# Hub.net
KiCad netlist of a schematic drawn in Altium Designer
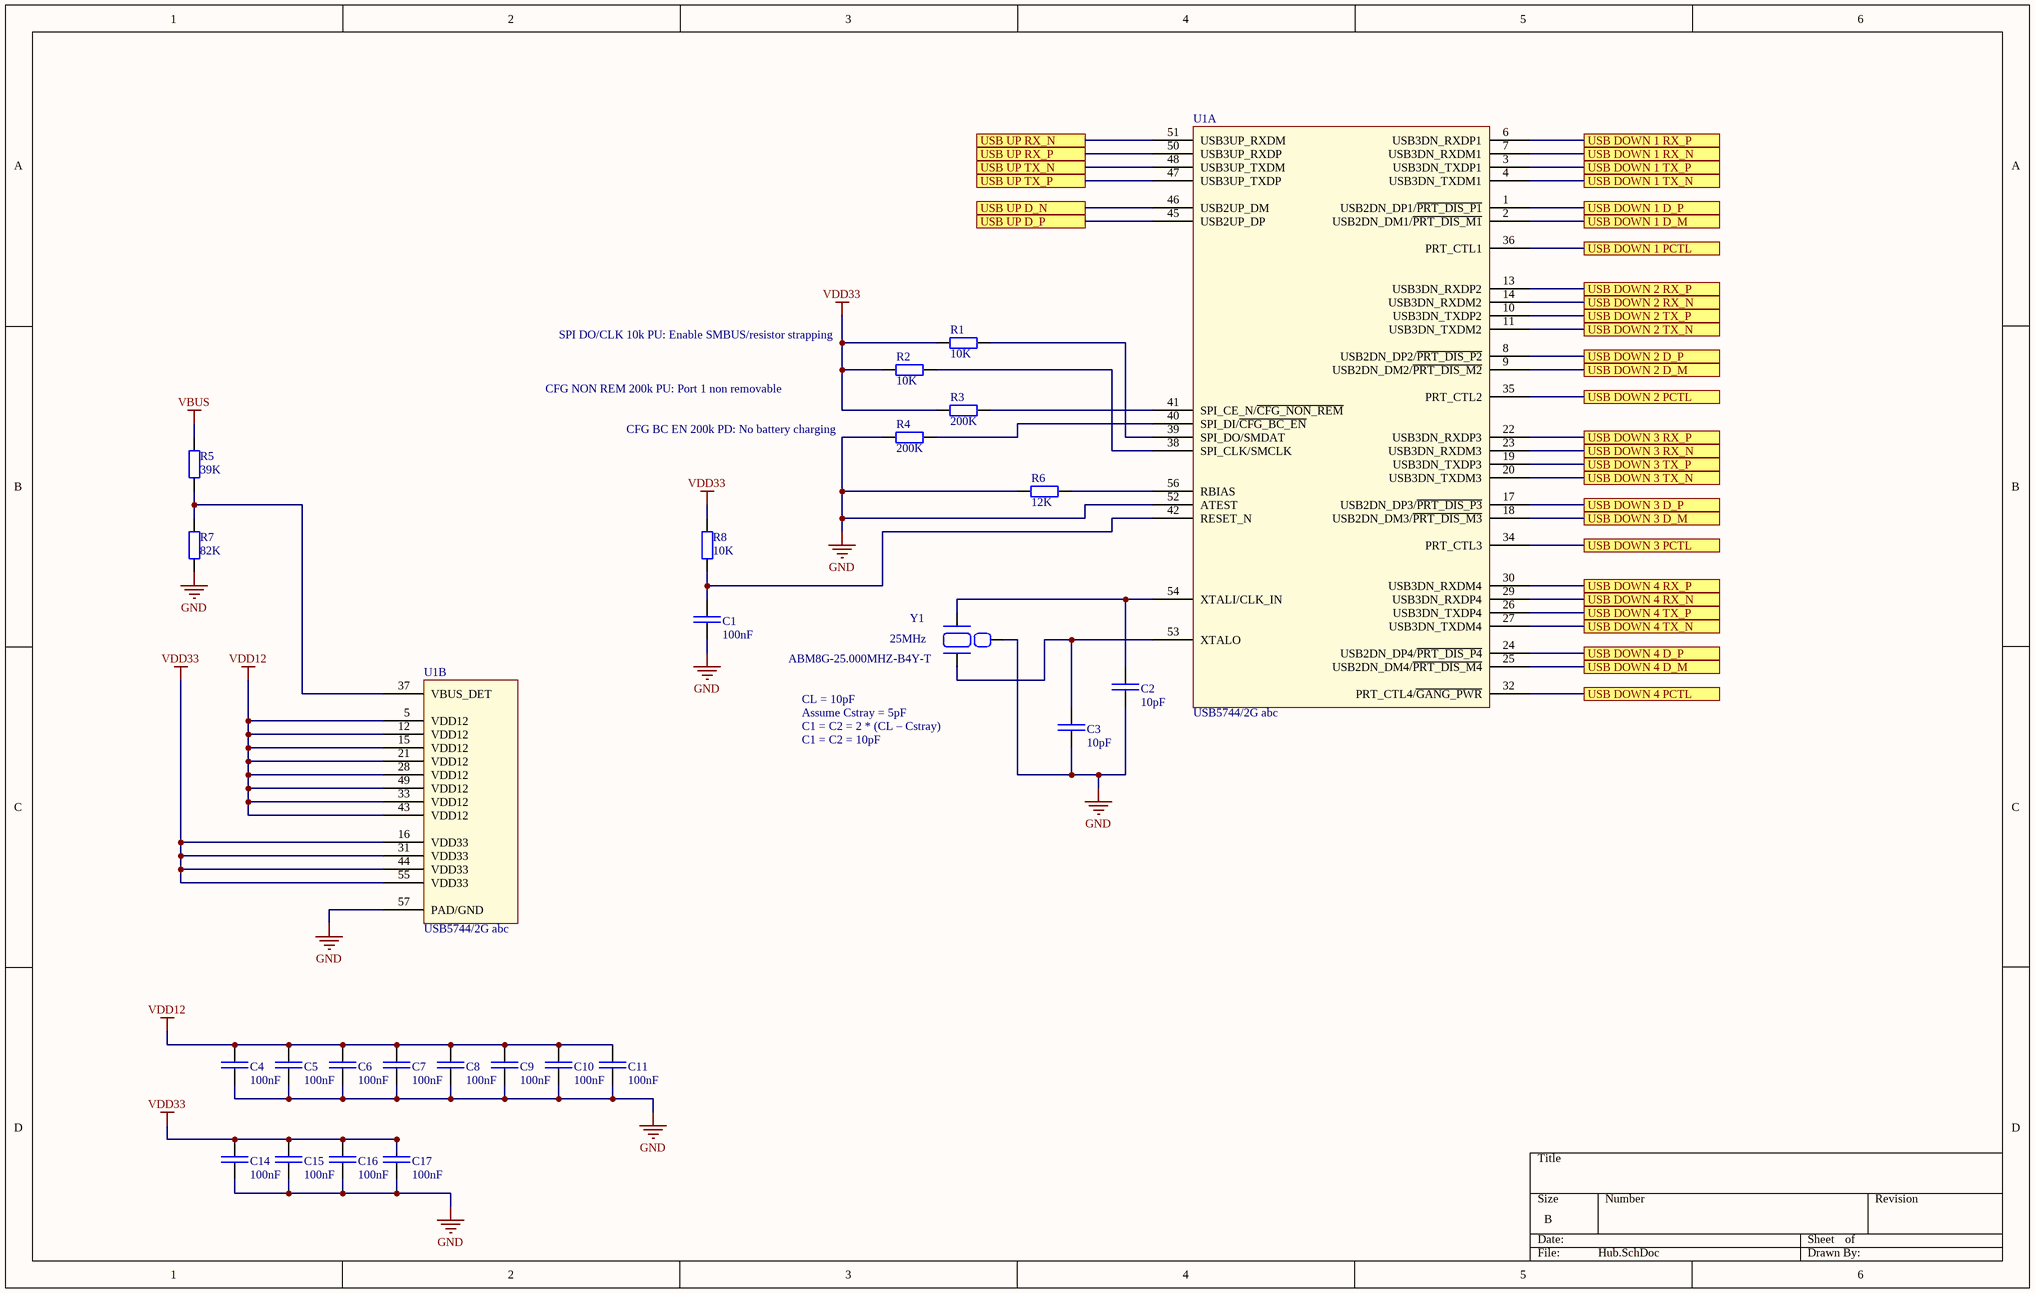
[diagram p0: Hub.SchDoc]

(export (version "E")
  (design (tool "Eeschema 10.0.6"))
  (components
    (comp (ref "C1")
      (value "100nF")
      (footprint "CAP_SM0603_YAGEOCC2_N")
      (description "CAP 100nF SM0603 X7R 50V YAGEO CC2")
      (fields
        (field (name "MANUFACTURER") "Yageo")
        (field (name "MANUFACTURER PART NUMBER") "CC0603KRX7R9BB104")
      )
      (libsource (lib "Yageo") (part "CC0603KRX7R9BB104"))
    )
    (comp (ref "C2")
      (value "10pF")
      (footprint "CAP_SM0603_YAGEOCC2_N")
      (description "CAP 10pF SM0603 NPO 50V YAGEO CC2")
      (fields
        (field (name "MANUFACTURER") "Yageo")
        (field (name "MANUFACTURER PART NUMBER") "CC0603JRNPO9BN100")
      )
      (libsource (lib "Yageo") (part "CC0603JRNPO9BN100"))
    )
    (comp (ref "C3")
      (value "10pF")
      (footprint "CAP_SM0603_YAGEOCC2_N")
      (description "CAP 10pF SM0603 NPO 50V YAGEO CC2")
      (fields
        (field (name "MANUFACTURER") "Yageo")
        (field (name "MANUFACTURER PART NUMBER") "CC0603JRNPO9BN100")
      )
      (libsource (lib "Yageo") (part "CC0603JRNPO9BN100"))
    )
    (comp (ref "C4")
      (value "100nF")
      (footprint "CAP_SM0603_YAGEOCC2_N")
      (description "CAP 100nF SM0603 X7R 50V YAGEO CC2")
      (fields
        (field (name "MANUFACTURER") "Yageo")
        (field (name "MANUFACTURER PART NUMBER") "CC0603KRX7R9BB104")
      )
      (libsource (lib "Yageo") (part "CC0603KRX7R9BB104"))
    )
    (comp (ref "C5")
      (value "100nF")
      (footprint "CAP_SM0603_YAGEOCC2_N")
      (description "CAP 100nF SM0603 X7R 50V YAGEO CC2")
      (fields
        (field (name "MANUFACTURER") "Yageo")
        (field (name "MANUFACTURER PART NUMBER") "CC0603KRX7R9BB104")
      )
      (libsource (lib "Yageo") (part "CC0603KRX7R9BB104"))
    )
    (comp (ref "C6")
      (value "100nF")
      (footprint "CAP_SM0603_YAGEOCC2_N")
      (description "CAP 100nF SM0603 X7R 50V YAGEO CC2")
      (fields
        (field (name "MANUFACTURER") "Yageo")
        (field (name "MANUFACTURER PART NUMBER") "CC0603KRX7R9BB104")
      )
      (libsource (lib "Yageo") (part "CC0603KRX7R9BB104"))
    )
    (comp (ref "C7")
      (value "100nF")
      (footprint "CAP_SM0603_YAGEOCC2_N")
      (description "CAP 100nF SM0603 X7R 50V YAGEO CC2")
      (fields
        (field (name "MANUFACTURER") "Yageo")
        (field (name "MANUFACTURER PART NUMBER") "CC0603KRX7R9BB104")
      )
      (libsource (lib "Yageo") (part "CC0603KRX7R9BB104"))
    )
    (comp (ref "C8")
      (value "100nF")
      (footprint "CAP_SM0603_YAGEOCC2_N")
      (description "CAP 100nF SM0603 X7R 50V YAGEO CC2")
      (fields
        (field (name "MANUFACTURER") "Yageo")
        (field (name "MANUFACTURER PART NUMBER") "CC0603KRX7R9BB104")
      )
      (libsource (lib "Yageo") (part "CC0603KRX7R9BB104"))
    )
    (comp (ref "C9")
      (value "100nF")
      (footprint "CAP_SM0603_YAGEOCC2_N")
      (description "CAP 100nF SM0603 X7R 50V YAGEO CC2")
      (fields
        (field (name "MANUFACTURER") "Yageo")
        (field (name "MANUFACTURER PART NUMBER") "CC0603KRX7R9BB104")
      )
      (libsource (lib "Yageo") (part "CC0603KRX7R9BB104"))
    )
    (comp (ref "C10")
      (value "100nF")
      (footprint "CAP_SM0603_YAGEOCC2_N")
      (description "CAP 100nF SM0603 X7R 50V YAGEO CC2")
      (fields
        (field (name "MANUFACTURER") "Yageo")
        (field (name "MANUFACTURER PART NUMBER") "CC0603KRX7R9BB104")
      )
      (libsource (lib "Yageo") (part "CC0603KRX7R9BB104"))
    )
    (comp (ref "C11")
      (value "100nF")
      (footprint "CAP_SM0603_YAGEOCC2_N")
      (description "CAP 100nF SM0603 X7R 50V YAGEO CC2")
      (fields
        (field (name "MANUFACTURER") "Yageo")
        (field (name "MANUFACTURER PART NUMBER") "CC0603KRX7R9BB104")
      )
      (libsource (lib "Yageo") (part "CC0603KRX7R9BB104"))
    )
    (comp (ref "C14")
      (value "100nF")
      (footprint "CAP_SM0603_YAGEOCC2_N")
      (description "CAP 100nF SM0603 X7R 50V YAGEO CC2")
      (fields
        (field (name "MANUFACTURER") "Yageo")
        (field (name "MANUFACTURER PART NUMBER") "CC0603KRX7R9BB104")
      )
      (libsource (lib "Yageo") (part "CC0603KRX7R9BB104"))
    )
    (comp (ref "C15")
      (value "100nF")
      (footprint "CAP_SM0603_YAGEOCC2_N")
      (description "CAP 100nF SM0603 X7R 50V YAGEO CC2")
      (fields
        (field (name "MANUFACTURER") "Yageo")
        (field (name "MANUFACTURER PART NUMBER") "CC0603KRX7R9BB104")
      )
      (libsource (lib "Yageo") (part "CC0603KRX7R9BB104"))
    )
    (comp (ref "C16")
      (value "100nF")
      (footprint "CAP_SM0603_YAGEOCC2_N")
      (description "CAP 100nF SM0603 X7R 50V YAGEO CC2")
      (fields
        (field (name "MANUFACTURER") "Yageo")
        (field (name "MANUFACTURER PART NUMBER") "CC0603KRX7R9BB104")
      )
      (libsource (lib "Yageo") (part "CC0603KRX7R9BB104"))
    )
    (comp (ref "C17")
      (value "100nF")
      (footprint "CAP_SM0603_YAGEOCC2_N")
      (description "CAP 100nF SM0603 X7R 50V YAGEO CC2")
      (fields
        (field (name "MANUFACTURER") "Yageo")
        (field (name "MANUFACTURER PART NUMBER") "CC0603KRX7R9BB104")
      )
      (libsource (lib "Yageo") (part "CC0603KRX7R9BB104"))
    )
    (comp (ref "R1")
      (value "10K")
      (footprint "RES_SM0603_YAGEORC_N")
      (description "RES 10K SM0603 YAGEO RC_L")
      (fields
        (field (name "MANUFACTURER") "Yageo")
        (field (name "MANUFACTURER PART NUMBER") "RC0603FR-0710KL")
      )
      (libsource (lib "") (part "RC0603FR-0710KL_1"))
    )
    (comp (ref "R2")
      (value "10K")
      (footprint "RES_SM0603_YAGEORC_N")
      (description "RES 10K SM0603 YAGEO RC_L")
      (fields
        (field (name "MANUFACTURER") "Yageo")
        (field (name "MANUFACTURER PART NUMBER") "RC0603FR-0710KL")
      )
      (libsource (lib "") (part "RC0603FR-0710KL_1"))
    )
    (comp (ref "R3")
      (value "200K")
      (footprint "RES_SM0603_YAGEORC_N")
      (description "RES 200K SM0603 YAGEO RC_L")
      (fields
        (field (name "MANUFACTURER") "Yageo")
        (field (name "MANUFACTURER PART NUMBER") "RC0603FR-07200KL")
      )
      (libsource (lib "Yageo") (part "RC0603FR-07200KL"))
    )
    (comp (ref "R4")
      (value "200K")
      (footprint "RES_SM0603_YAGEORC_N")
      (description "RES 200K SM0603 YAGEO RC_L")
      (fields
        (field (name "MANUFACTURER") "Yageo")
        (field (name "MANUFACTURER PART NUMBER") "RC0603FR-07200KL")
      )
      (libsource (lib "Yageo") (part "RC0603FR-07200KL"))
    )
    (comp (ref "R5")
      (value "39K")
      (footprint "RES_SM0603_YAGEORC_N")
      (description "RES 39K SM0603 YAGEO RC_L")
      (fields
        (field (name "MANUFACTURER") "Yageo")
        (field (name "MANUFACTURER PART NUMBER") "RC0603FR-0739KL")
      )
      (libsource (lib "Yageo") (part "RC0603FR-0739KL"))
    )
    (comp (ref "R6")
      (value "12K")
      (footprint "RES_SM0603_YAGEORC_N")
      (description "RES 12K SM0603 YAGEO RC_L")
      (fields
        (field (name "MANUFACTURER") "Yageo")
        (field (name "MANUFACTURER PART NUMBER") "RC0603FR-0712KL")
      )
      (libsource (lib "Yageo") (part "RC0603FR-0712KL"))
    )
    (comp (ref "R7")
      (value "82K")
      (footprint "RES_SM0603_YAGEORC_N")
      (description "RES 82K SM0603 YAGEO RC_L")
      (fields
        (field (name "MANUFACTURER") "Yageo")
        (field (name "MANUFACTURER PART NUMBER") "RC0603FR-0782KL")
      )
      (libsource (lib "Yageo") (part "RC0603FR-0782KL"))
    )
    (comp (ref "R8")
      (value "10K")
      (footprint "RES_SM0603_YAGEORC_N")
      (description "RES 10K SM0603 YAGEO RC_L")
      (fields
        (field (name "MANUFACTURER") "Yageo")
        (field (name "MANUFACTURER PART NUMBER") "RC0603FR-0710KL")
      )
      (libsource (lib "Yageo") (part "RC0603FR-0710KL"))
    )
    (comp (ref "U1")
      (value "USB5744/2G abc")
      (footprint "QFN40P700X700X100_HS-57N - USB5744/2G")
      (description "IC HUB CTLR USB 56VQFN")
      (libsource (lib "KBuchka-IntLib") (part "USB5744/2G abc"))
    )
    (comp (ref "Y1")
      (value "ABM8G-25.000MHZ-B4Y-T")
      (footprint "ABM8G-25.000MHZ-B4Y-T")
      (description "CRYSTAL 25.0000MHZ 10PF SMD")
      (libsource (lib "KBuchka-IntLib") (part "ABM8G-25.000MHZ-B4Y-T"))
    )
  )
  (nets
    (net (code "1") (name "/USB DOWN 1 D_M") (class "Default")
      (node (ref "U1") (pin "2") (pinfunction "USB2DN_DM1/~{PRT_DIS_M1}_2") (pintype "passive"))
    )
    (net (code "2") (name "/USB DOWN 1 D_P") (class "Default")
      (node (ref "U1") (pin "1") (pinfunction "USB2DN_DP1/~{PRT_DIS_P1}_1") (pintype "passive"))
    )
    (net (code "3") (name "/USB DOWN 1 PCTL") (class "Default")
      (node (ref "U1") (pin "36") (pinfunction "PRT_CTL1_36") (pintype "passive"))
    )
    (net (code "4") (name "/USB DOWN 1 RX_N") (class "Default")
      (node (ref "U1") (pin "7") (pinfunction "USB3DN_RXDM1_7") (pintype "passive"))
    )
    (net (code "5") (name "/USB DOWN 1 RX_P") (class "Default")
      (node (ref "U1") (pin "6") (pinfunction "USB3DN_RXDP1_6") (pintype "passive"))
    )
    (net (code "6") (name "/USB DOWN 1 TX_N") (class "Default")
      (node (ref "U1") (pin "4") (pinfunction "USB3DN_TXDM1_4") (pintype "passive"))
    )
    (net (code "7") (name "/USB DOWN 1 TX_P") (class "Default")
      (node (ref "U1") (pin "3") (pinfunction "USB3DN_TXDP1_3") (pintype "passive"))
    )
    (net (code "8") (name "/USB DOWN 2 D_M") (class "Default")
      (node (ref "U1") (pin "9") (pinfunction "USB2DN_DM2/~{PRT_DIS_M2}_9") (pintype "passive"))
    )
    (net (code "9") (name "/USB DOWN 2 D_P") (class "Default")
      (node (ref "U1") (pin "8") (pinfunction "USB2DN_DP2/~{PRT_DIS_P2}_8") (pintype "passive"))
    )
    (net (code "10") (name "/USB DOWN 2 PCTL") (class "Default")
      (node (ref "U1") (pin "35") (pinfunction "PRT_CTL2_35") (pintype "passive"))
    )
    (net (code "11") (name "/USB DOWN 2 RX_N") (class "Default")
      (node (ref "U1") (pin "14") (pinfunction "USB3DN_RXDM2_14") (pintype "passive"))
    )
    (net (code "12") (name "/USB DOWN 2 RX_P") (class "Default")
      (node (ref "U1") (pin "13") (pinfunction "USB3DN_RXDP2_13") (pintype "passive"))
    )
    (net (code "13") (name "/USB DOWN 2 TX_N") (class "Default")
      (node (ref "U1") (pin "11") (pinfunction "USB3DN_TXDM2_11") (pintype "passive"))
    )
    (net (code "14") (name "/USB DOWN 2 TX_P") (class "Default")
      (node (ref "U1") (pin "10") (pinfunction "USB3DN_TXDP2_10") (pintype "passive"))
    )
    (net (code "15") (name "/USB DOWN 3 D_M") (class "Default")
      (node (ref "U1") (pin "18") (pinfunction "USB2DN_DM3/~{PRT_DIS_M3}_18") (pintype "passive"))
    )
    (net (code "16") (name "/USB DOWN 3 D_P") (class "Default")
      (node (ref "U1") (pin "17") (pinfunction "USB2DN_DP3/~{PRT_DIS_P3}_17") (pintype "passive"))
    )
    (net (code "17") (name "/USB DOWN 3 PCTL") (class "Default")
      (node (ref "U1") (pin "34") (pinfunction "PRT_CTL3_34") (pintype "passive"))
    )
    (net (code "18") (name "/USB DOWN 3 RX_N") (class "Default")
      (node (ref "U1") (pin "23") (pinfunction "USB3DN_RXDM3_23") (pintype "passive"))
    )
    (net (code "19") (name "/USB DOWN 3 RX_P") (class "Default")
      (node (ref "U1") (pin "22") (pinfunction "USB3DN_RXDP3_22") (pintype "passive"))
    )
    (net (code "20") (name "/USB DOWN 3 TX_N") (class "Default")
      (node (ref "U1") (pin "20") (pinfunction "USB3DN_TXDM3_20") (pintype "passive"))
    )
    (net (code "21") (name "/USB DOWN 3 TX_P") (class "Default")
      (node (ref "U1") (pin "19") (pinfunction "USB3DN_TXDP3_19") (pintype "passive"))
    )
    (net (code "22") (name "/USB DOWN 4 D_M") (class "Default")
      (node (ref "U1") (pin "25") (pinfunction "USB2DN_DM4/~{PRT_DIS_M4}_25") (pintype "passive"))
    )
    (net (code "23") (name "/USB DOWN 4 D_P") (class "Default")
      (node (ref "U1") (pin "24") (pinfunction "USB2DN_DP4/~{PRT_DIS_P4}_24") (pintype "passive"))
    )
    (net (code "24") (name "/USB DOWN 4 PCTL") (class "Default")
      (node (ref "U1") (pin "32") (pinfunction "PRT_CTL4/~{GANG_PWR}_32") (pintype "passive"))
    )
    (net (code "25") (name "/USB DOWN 4 RX_N") (class "Default")
      (node (ref "U1") (pin "29") (pinfunction "USB3DN_RXDP4_29") (pintype "passive"))
    )
    (net (code "26") (name "/USB DOWN 4 RX_P") (class "Default")
      (node (ref "U1") (pin "30") (pinfunction "USB3DN_RXDM4_30") (pintype "passive"))
    )
    (net (code "27") (name "/USB DOWN 4 TX_N") (class "Default")
      (node (ref "U1") (pin "27") (pinfunction "USB3DN_TXDM4_27") (pintype "passive"))
    )
    (net (code "28") (name "/USB DOWN 4 TX_P") (class "Default")
      (node (ref "U1") (pin "26") (pinfunction "USB3DN_TXDP4_26") (pintype "passive"))
    )
    (net (code "29") (name "/USB UP D_N") (class "Default")
      (node (ref "U1") (pin "46") (pinfunction "USB2UP_DM_46") (pintype "passive"))
    )
    (net (code "30") (name "/USB UP D_P") (class "Default")
      (node (ref "U1") (pin "45") (pinfunction "USB2UP_DP_45") (pintype "passive"))
    )
    (net (code "31") (name "/USB UP RX_N") (class "Default")
      (node (ref "U1") (pin "51") (pinfunction "USB3UP_RXDM_51") (pintype "passive"))
    )
    (net (code "32") (name "/USB UP RX_P") (class "Default")
      (node (ref "U1") (pin "50") (pinfunction "USB3UP_RXDP_50") (pintype "passive"))
    )
    (net (code "33") (name "/USB UP TX_N") (class "Default")
      (node (ref "U1") (pin "48") (pinfunction "USB3UP_TXDM_48") (pintype "passive"))
    )
    (net (code "34") (name "/USB UP TX_P") (class "Default")
      (node (ref "U1") (pin "47") (pinfunction "USB3UP_TXDP_47") (pintype "passive"))
    )
    (net (code "35") (name "GND") (class "Default")
      (node (ref "C1") (pin "2") (pintype "passive"))
      (node (ref "C10") (pin "2") (pintype "passive"))
      (node (ref "C11") (pin "2") (pintype "passive"))
      (node (ref "C14") (pin "2") (pintype "passive"))
      (node (ref "C15") (pin "2") (pintype "passive"))
      (node (ref "C16") (pin "2") (pintype "passive"))
      (node (ref "C17") (pin "2") (pintype "passive"))
      (node (ref "C2") (pin "1") (pintype "passive"))
      (node (ref "C3") (pin "1") (pintype "passive"))
      (node (ref "C4") (pin "2") (pintype "passive"))
      (node (ref "C5") (pin "2") (pintype "passive"))
      (node (ref "C6") (pin "2") (pintype "passive"))
      (node (ref "C7") (pin "2") (pintype "passive"))
      (node (ref "C8") (pin "2") (pintype "passive"))
      (node (ref "C9") (pin "2") (pintype "passive"))
      (node (ref "R4") (pin "1") (pintype "passive"))
      (node (ref "R6") (pin "1") (pintype "passive"))
      (node (ref "R7") (pin "1") (pintype "passive"))
      (node (ref "U1") (pin "52") (pinfunction "ATEST_52") (pintype "passive"))
      (node (ref "U1") (pin "57") (pinfunction "PAD/GND_57") (pintype "passive"))
      (node (ref "Y1") (pin "GND") (pinfunction "4_GND") (pintype "passive"))
    )
    (net (code "36") (name "Net-(U1A-RBIAS)") (class "Default")
      (node (ref "R6") (pin "2") (pintype "passive"))
      (node (ref "U1") (pin "56") (pinfunction "RBIAS_56") (pintype "passive"))
    )
    (net (code "37") (name "Net-(U1A-RESET_N)") (class "Default")
      (node (ref "C1") (pin "1") (pintype "passive"))
      (node (ref "R8") (pin "1") (pintype "passive"))
      (node (ref "U1") (pin "42") (pinfunction "RESET_N_42") (pintype "passive"))
    )
    (net (code "38") (name "Net-(U1A-SPI_CE_N{slash}~{CFG_NON_REM})") (class "Default")
      (node (ref "R3") (pin "2") (pintype "passive"))
      (node (ref "U1") (pin "41") (pinfunction "SPI_CE_N/~{CFG_NON_REM}_41") (pintype "passive"))
    )
    (net (code "39") (name "Net-(U1A-SPI_CLK{slash}SMCLK)") (class "Default")
      (node (ref "R2") (pin "2") (pintype "passive"))
      (node (ref "U1") (pin "38") (pinfunction "SPI_CLK/SMCLK_38") (pintype "passive"))
    )
    (net (code "40") (name "Net-(U1A-SPI_DI{slash}~{CFG_BC_EN})") (class "Default")
      (node (ref "R4") (pin "2") (pintype "passive"))
      (node (ref "U1") (pin "40") (pinfunction "SPI_DI/~{CFG_BC_EN}_40") (pintype "passive"))
    )
    (net (code "41") (name "Net-(U1A-SPI_DO{slash}SMDAT)") (class "Default")
      (node (ref "R1") (pin "2") (pintype "passive"))
      (node (ref "U1") (pin "39") (pinfunction "SPI_DO/SMDAT_39") (pintype "passive"))
    )
    (net (code "42") (name "Net-(U1A-XTALI{slash}CLK_IN)") (class "Default")
      (node (ref "C2") (pin "2") (pintype "passive"))
      (node (ref "U1") (pin "54") (pinfunction "XTALI/CLK_IN_54") (pintype "passive"))
      (node (ref "Y1") (pin "1") (pinfunction "1_1") (pintype "passive"))
    )
    (net (code "43") (name "Net-(U1A-XTALO)") (class "Default")
      (node (ref "C3") (pin "2") (pintype "passive"))
      (node (ref "U1") (pin "53") (pinfunction "XTALO_53") (pintype "passive"))
      (node (ref "Y1") (pin "3") (pinfunction "3_3") (pintype "passive"))
    )
    (net (code "44") (name "Net-(U1B-VBUS_DET)") (class "Default")
      (node (ref "R5") (pin "1") (pintype "passive"))
      (node (ref "R7") (pin "2") (pintype "passive"))
      (node (ref "U1") (pin "37") (pinfunction "VBUS_DET_37") (pintype "passive"))
    )
    (net (code "45") (name "VBUS") (class "Default") (node (ref "R5") (pin "2") (pintype "passive")))
    (net (code "46") (name "VDD12") (class "Default")
      (node (ref "C10") (pin "1") (pintype "passive"))
      (node (ref "C11") (pin "1") (pintype "passive"))
      (node (ref "C4") (pin "1") (pintype "passive"))
      (node (ref "C5") (pin "1") (pintype "passive"))
      (node (ref "C6") (pin "1") (pintype "passive"))
      (node (ref "C7") (pin "1") (pintype "passive"))
      (node (ref "C8") (pin "1") (pintype "passive"))
      (node (ref "C9") (pin "1") (pintype "passive"))
      (node (ref "U1") (pin "12") (pinfunction "VDD12_12") (pintype "passive"))
      (node (ref "U1") (pin "15") (pinfunction "VDD12_15") (pintype "passive"))
      (node (ref "U1") (pin "21") (pinfunction "VDD12_21") (pintype "passive"))
      (node (ref "U1") (pin "28") (pinfunction "VDD12_28") (pintype "passive"))
      (node (ref "U1") (pin "33") (pinfunction "VDD12_33") (pintype "passive"))
      (node (ref "U1") (pin "43") (pinfunction "VDD12_43") (pintype "passive"))
      (node (ref "U1") (pin "49") (pinfunction "VDD12_49") (pintype "passive"))
      (node (ref "U1") (pin "5") (pinfunction "VDD12_5") (pintype "passive"))
    )
    (net (code "47") (name "VDD33") (class "Default")
      (node (ref "C14") (pin "1") (pintype "passive"))
      (node (ref "C15") (pin "1") (pintype "passive"))
      (node (ref "C16") (pin "1") (pintype "passive"))
      (node (ref "C17") (pin "1") (pintype "passive"))
      (node (ref "R1") (pin "1") (pintype "passive"))
      (node (ref "R2") (pin "1") (pintype "passive"))
      (node (ref "R3") (pin "1") (pintype "passive"))
      (node (ref "R8") (pin "2") (pintype "passive"))
      (node (ref "U1") (pin "16") (pinfunction "VDD33_16") (pintype "passive"))
      (node (ref "U1") (pin "31") (pinfunction "VDD33_31") (pintype "passive"))
      (node (ref "U1") (pin "44") (pinfunction "VDD33_44") (pintype "passive"))
      (node (ref "U1") (pin "55") (pinfunction "VDD33_55") (pintype "passive"))
    )
  )
)
